# miditendo_rev5.net
KiCad netlist of a schematic drawn in EAGLE
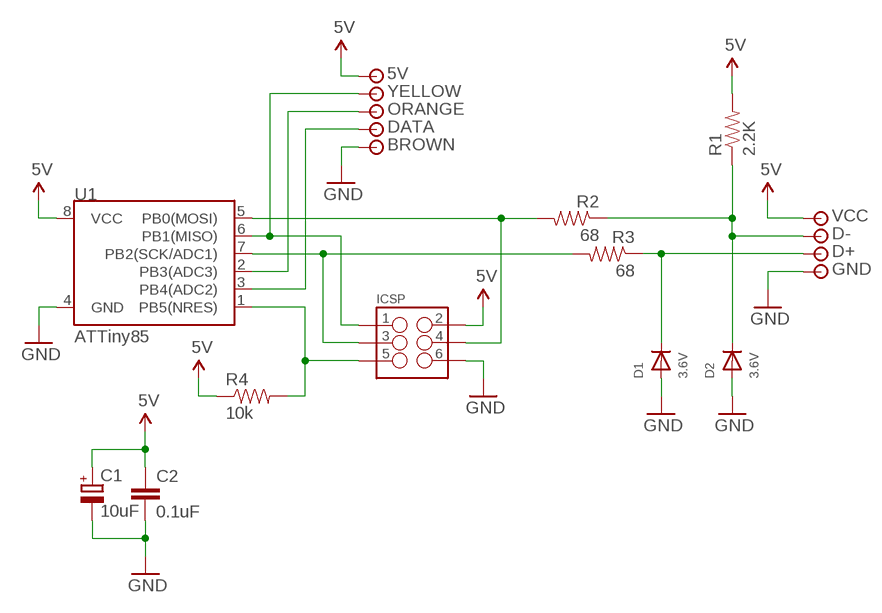
[diagram p0: schematic, sheet 1]

(export (version "E")
  (design (tool "Eeschema 10.0.6"))
  (components
    (comp (ref "5V")
      (value "WIRE_JOINT")
      (footprint "eagle-import:THSOLDERPOINT")
      (libsource (lib "eagle-import") (part "WIRE_JOINT"))
    )
    (comp (ref "BROWN")
      (value "WIRE_JOINT")
      (footprint "eagle-import:THSOLDERPOINT")
      (libsource (lib "eagle-import") (part "WIRE_JOINT"))
    )
    (comp (ref "C1")
      (value "10uF")
      (footprint "eagle-import:PANASONIC_B")
      (libsource (lib "eagle-import") (part "CPOL-EUB"))
    )
    (comp (ref "C2")
      (value "0.1uF")
      (footprint "eagle-import:C0805")
      (libsource (lib "eagle-import") (part "C-EUC0805"))
    )
    (comp (ref "D+")
      (value "WIRE_JOINT")
      (footprint "eagle-import:THSOLDERPOINT")
      (libsource (lib "eagle-import") (part "WIRE_JOINT"))
    )
    (comp (ref "D-")
      (value "WIRE_JOINT")
      (footprint "eagle-import:THSOLDERPOINT")
      (libsource (lib "eagle-import") (part "WIRE_JOINT"))
    )
    (comp (ref "D1")
      (value "3.6V")
      (footprint "eagle-import:SOD-123")
      (libsource (lib "eagle-import") (part "DIODESOD-123"))
    )
    (comp (ref "D2")
      (value "3.6V")
      (footprint "eagle-import:SOD-123")
      (libsource (lib "eagle-import") (part "DIODESOD-123"))
    )
    (comp (ref "DATA")
      (value "WIRE_JOINT")
      (footprint "eagle-import:THSOLDERPOINT")
      (libsource (lib "eagle-import") (part "WIRE_JOINT"))
    )
    (comp (ref "GND")
      (value "WIRE_JOINT")
      (footprint "eagle-import:THSOLDERPOINT")
      (libsource (lib "eagle-import") (part "WIRE_JOINT"))
    )
    (comp (ref "ICSP")
      (value "M03X2SMT")
      (footprint "eagle-import:2X3_SMT_POSTS")
      (libsource (lib "eagle-import") (part "M03X2SMT"))
    )
    (comp (ref "ORANGE")
      (value "WIRE_JOINT")
      (footprint "eagle-import:THSOLDERPOINT")
      (libsource (lib "eagle-import") (part "WIRE_JOINT"))
    )
    (comp (ref "R1")
      (value "2.2K")
      (footprint "eagle-import:0805")
      (libsource (lib "eagle-import") (part "RESISTOR0805"))
    )
    (comp (ref "R2")
      (value "68")
      (footprint "eagle-import:0805")
      (libsource (lib "eagle-import") (part "RESISTOR0805"))
    )
    (comp (ref "R3")
      (value "68")
      (footprint "eagle-import:0805")
      (libsource (lib "eagle-import") (part "RESISTOR0805"))
    )
    (comp (ref "R4")
      (value "10k")
      (footprint "eagle-import:0805")
      (libsource (lib "eagle-import") (part "RESISTOR0805"))
    )
    (comp (ref "U1")
      (value "ATTiny85")
      (footprint "eagle-import:SO08-EIAJ")
      (libsource (lib "eagle-import") (part "ATTINY45TINY85-20-SMT"))
    )
    (comp (ref "VCC")
      (value "WIRE_JOINT")
      (footprint "eagle-import:THSOLDERPOINT")
      (libsource (lib "eagle-import") (part "WIRE_JOINT"))
    )
    (comp (ref "YELLOW")
      (value "WIRE_JOINT")
      (footprint "eagle-import:THSOLDERPOINT")
      (libsource (lib "eagle-import") (part "WIRE_JOINT"))
    )
  )
  (nets
    (net (code "1") (name "5V") (class "Default")
      (node (ref "5V") (pin "P$1") (pinfunction "P$1_P$1") (pintype "passive"))
      (node (ref "C1") (pin "+") (pinfunction "+_+") (pintype "passive"))
      (node (ref "C2") (pin "1") (pinfunction "1_1") (pintype "passive"))
      (node (ref "ICSP") (pin "2") (pinfunction "2_2") (pintype "bidirectional"))
      (node (ref "R1") (pin "2") (pinfunction "2_2") (pintype "passive"))
      (node (ref "R4") (pin "1") (pinfunction "1_1") (pintype "passive"))
      (node (ref "U1") (pin "8") (pinfunction "VCC_8") (pintype "bidirectional"))
      (node (ref "VCC") (pin "P$1") (pinfunction "P$1_P$1") (pintype "passive"))
    )
    (net (code "2") (name "GND") (class "Default")
      (node (ref "BROWN") (pin "P$1") (pinfunction "P$1_P$1") (pintype "passive"))
      (node (ref "C1") (pin "-") (pinfunction "-_-") (pintype "passive"))
      (node (ref "C2") (pin "2") (pinfunction "2_2") (pintype "passive"))
      (node (ref "D1") (pin "A") (pinfunction "A_A") (pintype "passive"))
      (node (ref "D2") (pin "A") (pinfunction "A_A") (pintype "passive"))
      (node (ref "GND") (pin "P$1") (pinfunction "P$1_P$1") (pintype "passive"))
      (node (ref "ICSP") (pin "6") (pinfunction "6_6") (pintype "bidirectional"))
      (node (ref "U1") (pin "4") (pinfunction "GND_4") (pintype "bidirectional"))
    )
    (net (code "3") (name "Net-(D+-PadP$1)") (class "Default")
      (node (ref "D+") (pin "P$1") (pinfunction "P$1_P$1") (pintype "passive"))
      (node (ref "D1") (pin "C") (pinfunction "C_C") (pintype "passive"))
      (node (ref "R3") (pin "1") (pinfunction "1_1") (pintype "passive"))
    )
    (net (code "4") (name "Net-(D--PadP$1)") (class "Default")
      (node (ref "D-") (pin "P$1") (pinfunction "P$1_P$1") (pintype "passive"))
      (node (ref "D2") (pin "C") (pinfunction "C_C") (pintype "passive"))
      (node (ref "R1") (pin "1") (pinfunction "1_1") (pintype "passive"))
      (node (ref "R2") (pin "1") (pinfunction "1_1") (pintype "passive"))
    )
    (net (code "5") (name "Net-(U1-PB0(MOSI))") (class "Default")
      (node (ref "ICSP") (pin "4") (pinfunction "4_4") (pintype "bidirectional"))
      (node (ref "R2") (pin "2") (pinfunction "2_2") (pintype "passive"))
      (node (ref "U1") (pin "5") (pinfunction "PB0(MOSI)_5") (pintype "bidirectional"))
    )
    (net (code "6") (name "Net-(U1-PB1(MISO))") (class "Default")
      (node (ref "ICSP") (pin "1") (pinfunction "1_1") (pintype "bidirectional"))
      (node (ref "U1") (pin "6") (pinfunction "PB1(MISO)_6") (pintype "bidirectional"))
      (node (ref "YELLOW") (pin "P$1") (pinfunction "P$1_P$1") (pintype "passive"))
    )
    (net (code "7") (name "Net-(U1-PB2(SCK{slash}ADC1))") (class "Default")
      (node (ref "ICSP") (pin "3") (pinfunction "3_3") (pintype "bidirectional"))
      (node (ref "R3") (pin "2") (pinfunction "2_2") (pintype "passive"))
      (node (ref "U1") (pin "7") (pinfunction "PB2(SCK/ADC1)_7") (pintype "bidirectional"))
    )
    (net (code "8") (name "Net-(U1-PB3(ADC3))") (class "Default")
      (node (ref "ORANGE") (pin "P$1") (pinfunction "P$1_P$1") (pintype "passive"))
      (node (ref "U1") (pin "2") (pinfunction "PB3(ADC3)_2") (pintype "bidirectional"))
    )
    (net (code "9") (name "Net-(U1-PB4(ADC2))") (class "Default")
      (node (ref "DATA") (pin "P$1") (pinfunction "P$1_P$1") (pintype "passive"))
      (node (ref "U1") (pin "3") (pinfunction "PB4(ADC2)_3") (pintype "bidirectional"))
    )
    (net (code "10") (name "Net-(U1-PB5(NRES))") (class "Default")
      (node (ref "ICSP") (pin "5") (pinfunction "5_5") (pintype "bidirectional"))
      (node (ref "R4") (pin "2") (pinfunction "2_2") (pintype "passive"))
      (node (ref "U1") (pin "1") (pinfunction "PB5(NRES)_1") (pintype "bidirectional"))
    )
  )
)
